# SDC_2.net
KiCad netlist of a schematic drawn in Altium Designer
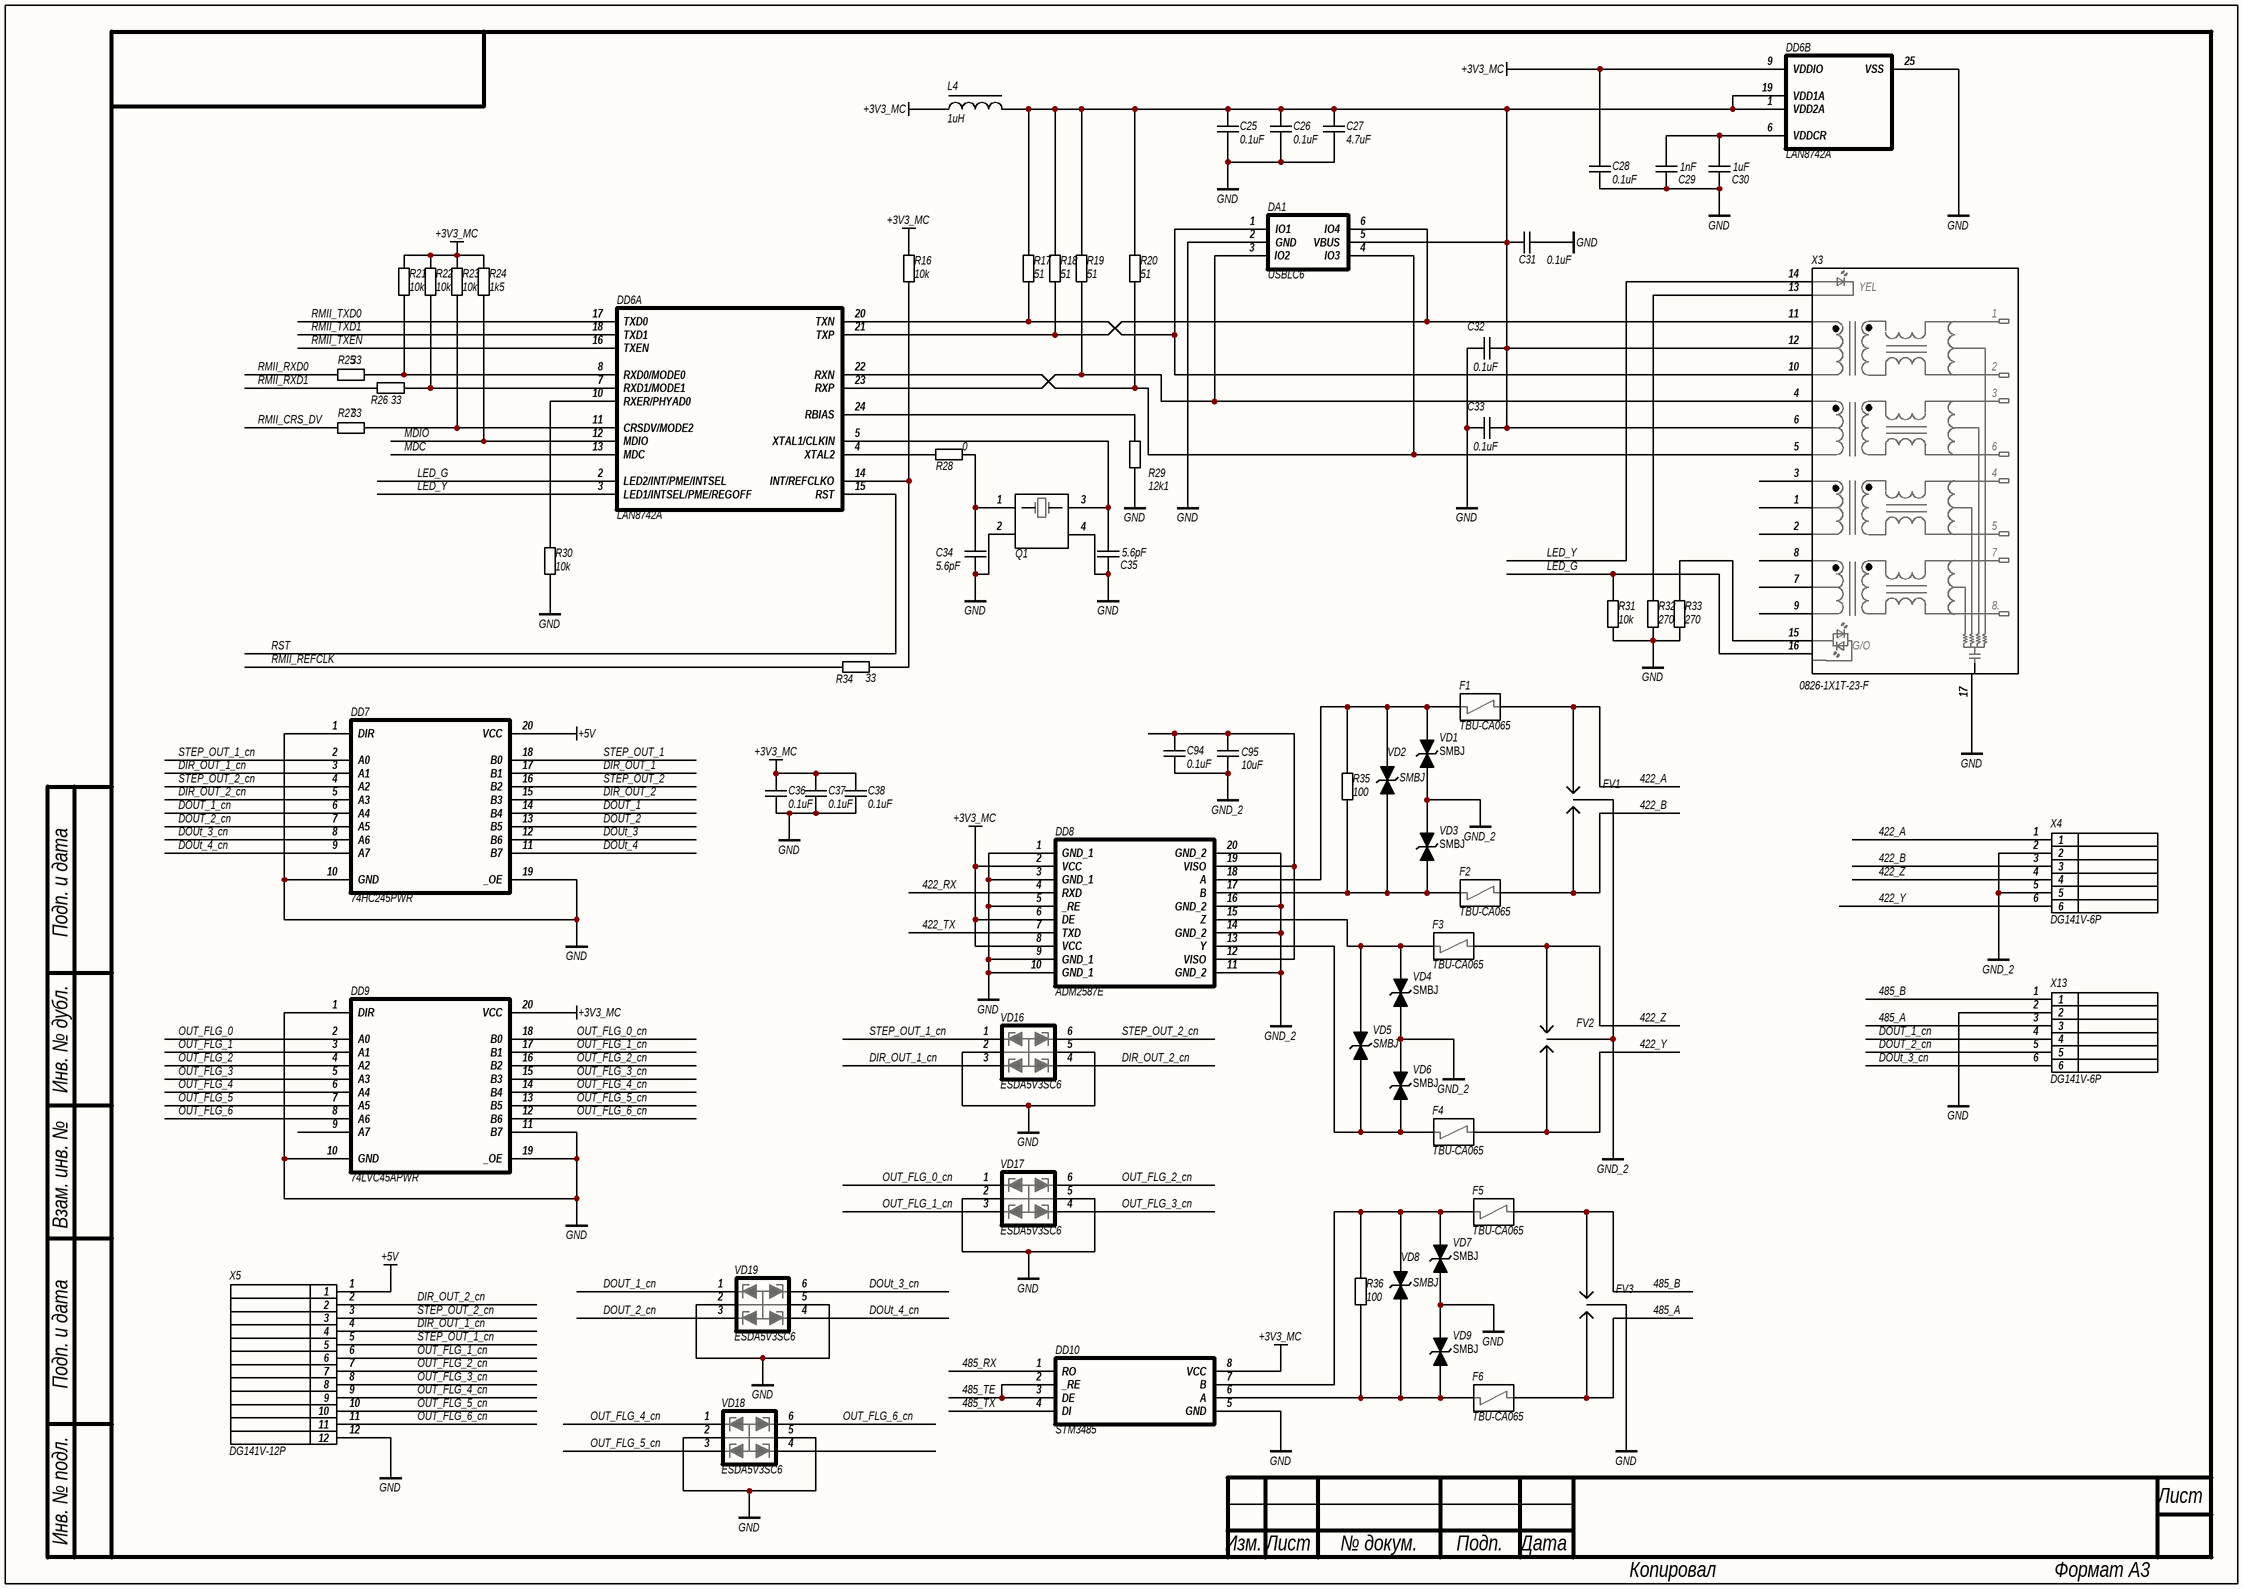
[diagram p0: SDC_2.SchDoc]

(export (version "E")
  (design (tool "Eeschema 10.0.6"))
  (components
    (comp (ref "C25")
      (value "0.1uF")
      (footprint "C0603")
      (description "SMD Capacitor")
      (fields (field (name "MANUFACTURER") "Murata") (field (name "TOLERANCE") "10%"))
      (libsource (lib "VKA") (part "CAP"))
    )
    (comp (ref "C26")
      (value "0.1uF")
      (footprint "C0603")
      (description "SMD Capacitor")
      (fields (field (name "MANUFACTURER") "Murata") (field (name "TOLERANCE") "10%"))
      (libsource (lib "VKA") (part "CAP"))
    )
    (comp (ref "C27")
      (value "4.7uF")
      (footprint "C0603")
      (description "SMD Capacitor")
      (fields (field (name "MANUFACTURER") "Murata") (field (name "TOLERANCE") "10%"))
      (libsource (lib "VKA") (part "CAP"))
    )
    (comp (ref "C28")
      (value "0.1uF")
      (footprint "C0603")
      (description "SMD Capacitor")
      (fields (field (name "MANUFACTURER") "Murata") (field (name "TOLERANCE") "10%"))
      (libsource (lib "VKA") (part "CAP"))
    )
    (comp (ref "C29")
      (value "1nF")
      (footprint "C0603")
      (description "SMD Capacitor")
      (fields (field (name "MANUFACTURER") "Murata") (field (name "TOLERANCE") "10%"))
      (libsource (lib "VKA") (part "CAP"))
    )
    (comp (ref "C30")
      (value "1uF")
      (footprint "C0603")
      (description "SMD Capacitor")
      (fields (field (name "MANUFACTURER") "Murata") (field (name "TOLERANCE") "10%"))
      (libsource (lib "VKA") (part "CAP"))
    )
    (comp (ref "C31")
      (value "0.1uF")
      (footprint "C0603")
      (description "SMD Capacitor")
      (fields (field (name "MANUFACTURER") "Murata") (field (name "TOLERANCE") "10%"))
      (libsource (lib "VKA") (part "CAP"))
    )
    (comp (ref "C32")
      (value "0.1uF")
      (footprint "C0603")
      (description "SMD Capacitor")
      (fields (field (name "MANUFACTURER") "Murata") (field (name "TOLERANCE") "10%"))
      (libsource (lib "VKA") (part "CAP"))
    )
    (comp (ref "C33")
      (value "0.1uF")
      (footprint "C0603")
      (description "SMD Capacitor")
      (fields (field (name "MANUFACTURER") "Murata") (field (name "TOLERANCE") "10%"))
      (libsource (lib "VKA") (part "CAP"))
    )
    (comp (ref "C34")
      (value "5.6pF")
      (footprint "C0603")
      (description "SMD Capacitor")
      (fields (field (name "MANUFACTURER") "Murata") (field (name "TOLERANCE") "10%"))
      (libsource (lib "VKA") (part "CAP"))
    )
    (comp (ref "C35")
      (value "5.6pF")
      (footprint "C0603")
      (description "SMD Capacitor")
      (fields (field (name "MANUFACTURER") "Murata") (field (name "TOLERANCE") "10%"))
      (libsource (lib "VKA") (part "CAP"))
    )
    (comp (ref "C36")
      (value "0.1uF")
      (footprint "C0603")
      (description "SMD Capacitor")
      (fields (field (name "MANUFACTURER") "Murata") (field (name "TOLERANCE") "10%"))
      (libsource (lib "VKA") (part "CAP"))
    )
    (comp (ref "C37")
      (value "0.1uF")
      (footprint "C0603")
      (description "SMD Capacitor")
      (fields (field (name "MANUFACTURER") "Murata") (field (name "TOLERANCE") "10%"))
      (libsource (lib "VKA") (part "CAP"))
    )
    (comp (ref "C38")
      (value "0.1uF")
      (footprint "C0603")
      (description "SMD Capacitor")
      (fields (field (name "MANUFACTURER") "Murata") (field (name "TOLERANCE") "10%"))
      (libsource (lib "VKA") (part "CAP"))
    )
    (comp (ref "C94")
      (value "0.1uF")
      (footprint "C0603")
      (description "SMD Capacitor")
      (fields (field (name "MANUFACTURER") "Murata") (field (name "TOLERANCE") "10%"))
      (libsource (lib "VKA") (part "CAP"))
    )
    (comp (ref "C95")
      (value "10uF")
      (footprint "C1210")
      (description "SMD Capacitor")
      (fields (field (name "MANUFACTURER") "Murata") (field (name "TOLERANCE") "10%"))
      (libsource (lib "VKA") (part "CAP"))
    )
    (comp (ref "DA1")
      (value "USBLC6")
      (footprint "ESD_SOT23-6L")
      (description "ESD protection Very low capacitance")
      (fields (field (name "MANUFACTURER") "ST"))
      (libsource (lib "VKA") (part "USBLC6-4SC6"))
    )
    (comp (ref "DD6")
      (value "LAN8742A")
      (footprint "QFN-MJ24")
      (description "RMII 10/100 Ethernet PHY")
      (libsource (lib "VKA") (part "LAN8742A"))
    )
    (comp (ref "DD7") (value "74HC245PWR") (footprint "TSSOP20") (libsource (lib "VKA") (part "74HC245PWR")))
    (comp (ref "DD8")
      (value "ADM2587E")
      (footprint "SOIC_20W")
      (description "RS485 isolator")
      (libsource (lib "VKA") (part "ADM2587E"))
    )
    (comp (ref "DD9")
      (value "74LVC45APWR")
      (footprint "TSSOP20")
      (libsource (lib "VKA") (part "74LVC45APWR"))
    )
    (comp (ref "DD10")
      (value "STM3485")
      (footprint "SO8_L")
      (description "RS485_tranciever")
      (libsource (lib "VKA") (part "ST3485EB"))
    )
    (comp (ref "F1")
      (value "TBU-CA065")
      (footprint "TBU-CA")
      (description "TBU fuse")
      (libsource (lib "VKA") (part "TBU-CA065"))
    )
    (comp (ref "F2")
      (value "TBU-CA065")
      (footprint "TBU-CA")
      (description "TBU fuse")
      (libsource (lib "VKA") (part "TBU-CA065"))
    )
    (comp (ref "F3")
      (value "TBU-CA065")
      (footprint "TBU-CA")
      (description "TBU fuse")
      (libsource (lib "VKA") (part "TBU-CA065"))
    )
    (comp (ref "F4")
      (value "TBU-CA065")
      (footprint "TBU-CA")
      (description "TBU fuse")
      (libsource (lib "VKA") (part "TBU-CA065"))
    )
    (comp (ref "F5")
      (value "TBU-CA065")
      (footprint "TBU-CA")
      (description "TBU fuse")
      (libsource (lib "VKA") (part "TBU-CA065"))
    )
    (comp (ref "F6")
      (value "TBU-CA065")
      (footprint "TBU-CA")
      (description "TBU fuse")
      (libsource (lib "VKA") (part "TBU-CA065"))
    )
    (comp (ref "FV1")
      (value "2030-42T-SM")
      (footprint "2030-42T-SM")
      (description "Charger")
      (libsource (lib "VKA") (part "2030-42T-SM"))
    )
    (comp (ref "FV2")
      (value "2030-42T-SM")
      (footprint "2030-42T-SM")
      (description "Charger")
      (libsource (lib "VKA") (part "2030-42T-SM"))
    )
    (comp (ref "FV3")
      (value "2030-42T-SM")
      (footprint "2030-42T-SM")
      (description "Charger")
      (libsource (lib "VKA") (part "2030-42T-SM"))
    )
    (comp (ref "L4")
      (value "1uH")
      (footprint "LQH32CN")
      (description "chip inductor")
      (fields (field (name "Comment") "LQH32CN"))
      (libsource (lib "VKA") (part "LQH32CN"))
    )
    (comp (ref "Q1")
      (value "NX2016SA")
      (footprint "CRY_NX2016SA_4P")
      (description "Crystal oscillator 25MHz")
      (fields (field (name "MANUFACTURER") "NDK"))
      (libsource (lib "VKA") (part "NX2016SA"))
    )
    (comp (ref "R16")
      (value "10k")
      (footprint "R0603")
      (description "SMD Resistor")
      (fields (field (name "POWER") "0.062 Wt") (field (name "TOLERANCE") "5%"))
      (libsource (lib "") (part "RES_1"))
    )
    (comp (ref "R17")
      (value "51")
      (footprint "R0603")
      (description "SMD Resistor")
      (fields (field (name "POWER") "0.062 Wt") (field (name "TOLERANCE") "5%"))
      (libsource (lib "VKA") (part "RES"))
    )
    (comp (ref "R18")
      (value "51")
      (footprint "R0603")
      (description "SMD Resistor")
      (fields (field (name "POWER") "0.062 Wt") (field (name "TOLERANCE") "5%"))
      (libsource (lib "VKA") (part "RES"))
    )
    (comp (ref "R19")
      (value "51")
      (footprint "R0603")
      (description "SMD Resistor")
      (fields (field (name "POWER") "0.062 Wt") (field (name "TOLERANCE") "5%"))
      (libsource (lib "VKA") (part "RES"))
    )
    (comp (ref "R20")
      (value "51")
      (footprint "R0603")
      (description "SMD Resistor")
      (fields (field (name "POWER") "0.062 Wt") (field (name "TOLERANCE") "5%"))
      (libsource (lib "VKA") (part "RES"))
    )
    (comp (ref "R21")
      (value "10k")
      (footprint "R0603")
      (description "SMD Resistor")
      (fields (field (name "POWER") "0.062 Wt") (field (name "TOLERANCE") "5%"))
      (libsource (lib "") (part "RES_1"))
    )
    (comp (ref "R22")
      (value "10k")
      (footprint "R0603")
      (description "SMD Resistor")
      (fields (field (name "POWER") "0.062 Wt") (field (name "TOLERANCE") "5%"))
      (libsource (lib "") (part "RES_1"))
    )
    (comp (ref "R23")
      (value "10k")
      (footprint "R0603")
      (description "SMD Resistor")
      (fields (field (name "POWER") "0.062 Wt") (field (name "TOLERANCE") "5%"))
      (libsource (lib "") (part "RES_1"))
    )
    (comp (ref "R24")
      (value "1k5")
      (footprint "R0603")
      (description "SMD Resistor")
      (fields (field (name "POWER") "0.062 Wt") (field (name "TOLERANCE") "5%"))
      (libsource (lib "") (part "RES_1"))
    )
    (comp (ref "R25")
      (value "33")
      (footprint "R0603")
      (description "SMD Resistor")
      (fields (field (name "POWER") "0.062 Wt") (field (name "TOLERANCE") "5%"))
      (libsource (lib "") (part "RES_2"))
    )
    (comp (ref "R26")
      (value "33")
      (footprint "R0603")
      (description "SMD Resistor")
      (fields (field (name "POWER") "0.062 Wt") (field (name "TOLERANCE") "5%"))
      (libsource (lib "") (part "RES_2"))
    )
    (comp (ref "R27")
      (value "33")
      (footprint "R0603")
      (description "SMD Resistor")
      (fields (field (name "POWER") "0.062 Wt") (field (name "TOLERANCE") "5%"))
      (libsource (lib "") (part "RES_2"))
    )
    (comp (ref "R28")
      (value "0")
      (footprint "R0603")
      (description "SMD Resistor")
      (fields (field (name "POWER") "0.062 Wt") (field (name "TOLERANCE") "5%"))
      (libsource (lib "") (part "RES_2"))
    )
    (comp (ref "R29")
      (value "12k1")
      (footprint "R0603")
      (description "SMD Resistor")
      (fields (field (name "POWER") "0.062 Wt") (field (name "TOLERANCE") "5%"))
      (libsource (lib "VKA") (part "RES"))
    )
    (comp (ref "R30")
      (value "10k")
      (footprint "R0603")
      (description "SMD Resistor")
      (fields (field (name "POWER") "0.062 Wt") (field (name "TOLERANCE") "5%"))
      (libsource (lib "VKA") (part "RES"))
    )
    (comp (ref "R31")
      (value "10k")
      (footprint "R0603")
      (description "SMD Resistor")
      (fields (field (name "POWER") "0.062 Wt") (field (name "TOLERANCE") "5%"))
      (libsource (lib "VKA") (part "RES"))
    )
    (comp (ref "R32")
      (value "270")
      (footprint "R0603")
      (description "SMD Resistor")
      (fields (field (name "POWER") "0.062 Wt") (field (name "TOLERANCE") "5%"))
      (libsource (lib "VKA") (part "RES"))
    )
    (comp (ref "R33")
      (value "270")
      (footprint "R0603")
      (description "SMD Resistor")
      (fields (field (name "POWER") "0.062 Wt") (field (name "TOLERANCE") "5%"))
      (libsource (lib "VKA") (part "RES"))
    )
    (comp (ref "R34")
      (value "33")
      (footprint "R0603")
      (description "SMD Resistor")
      (fields (field (name "POWER") "0.062 Wt") (field (name "TOLERANCE") "5%"))
      (libsource (lib "") (part "RES_2"))
    )
    (comp (ref "R35")
      (value "100")
      (footprint "R0603")
      (description "SMD Resistor")
      (fields (field (name "POWER") "0.062 Wt") (field (name "TOLERANCE") "5%"))
      (libsource (lib "") (part "RES_1"))
    )
    (comp (ref "R36")
      (value "100")
      (footprint "R0603")
      (description "SMD Resistor")
      (fields (field (name "POWER") "0.062 Wt") (field (name "TOLERANCE") "5%"))
      (libsource (lib "") (part "RES_1"))
    )
    (comp (ref "VD1")
      (value "SMBJ")
      (footprint "SMB-DO214")
      (description "TVS diode")
      (libsource (lib "VKA") (part "SMBJ5CA"))
    )
    (comp (ref "VD2")
      (value "SMBJ")
      (footprint "SMB-DO214")
      (description "TVSdiode")
      (libsource (lib "VKA") (part "SMBJ12CA"))
    )
    (comp (ref "VD3")
      (value "SMBJ")
      (footprint "SMB-DO214")
      (description "TVS diode")
      (libsource (lib "VKA") (part "SMBJ5CA"))
    )
    (comp (ref "VD4")
      (value "SMBJ")
      (footprint "SMB-DO214")
      (description "TVS diode")
      (libsource (lib "VKA") (part "SMBJ5CA"))
    )
    (comp (ref "VD5")
      (value "SMBJ")
      (footprint "SMB-DO214")
      (description "TVSdiode")
      (libsource (lib "VKA") (part "SMBJ12CA"))
    )
    (comp (ref "VD6")
      (value "SMBJ")
      (footprint "SMB-DO214")
      (description "TVS diode")
      (libsource (lib "VKA") (part "SMBJ5CA"))
    )
    (comp (ref "VD7")
      (value "SMBJ")
      (footprint "SMB-DO214")
      (description "TVS diode")
      (libsource (lib "VKA") (part "SMBJ5CA"))
    )
    (comp (ref "VD8")
      (value "SMBJ")
      (footprint "SMB-DO214")
      (description "TVSdiode")
      (libsource (lib "VKA") (part "SMBJ12CA"))
    )
    (comp (ref "VD9")
      (value "SMBJ")
      (footprint "SMB-DO214")
      (description "TVS diode")
      (libsource (lib "VKA") (part "SMBJ5CA"))
    )
    (comp (ref "VD16")
      (value "ESDA5V3SC6")
      (footprint "SOT23-6")
      (description "4-line ESD protection")
      (libsource (lib "VKA") (part "ESDA5V3SC6"))
    )
    (comp (ref "VD17")
      (value "ESDA5V3SC6")
      (footprint "SOT23-6")
      (description "4-line ESD protection")
      (libsource (lib "VKA") (part "ESDA5V3SC6"))
    )
    (comp (ref "VD18")
      (value "ESDA5V3SC6")
      (footprint "SOT23-6")
      (description "4-line ESD protection")
      (libsource (lib "VKA") (part "ESDA5V3SC6"))
    )
    (comp (ref "VD19")
      (value "ESDA5V3SC6")
      (footprint "SOT23-6")
      (description "4-line ESD protection")
      (libsource (lib "VKA") (part "ESDA5V3SC6"))
    )
    (comp (ref "X3")
      (value "0826-1X1T-23-F")
      (footprint "0826-1X1T-23F")
      (description "1Gb connector")
      (libsource (lib "VKA") (part "0826-1X1T-23-F"))
    )
    (comp (ref "X4")
      (value "DG141V-6P")
      (footprint "DG141V-06P")
      (description "wire connector")
      (libsource (lib "VKA") (part "DG141V-6P"))
    )
    (comp (ref "X5")
      (value "DG141V-12P")
      (footprint "DG141V-12P")
      (description "wire connector")
      (libsource (lib "VKA") (part "DG141V-12P"))
    )
    (comp (ref "X13")
      (value "DG141V-6P")
      (footprint "DG141V-06P")
      (description "wire connector")
      (libsource (lib "VKA") (part "DG141V-6P"))
    )
  )
  (nets
    (net (code "1") (name "+3V3_MC") (class "Default")
      (node (ref "C28") (pin "2") (pinfunction "2_2") (pintype "passive"))
      (node (ref "C36") (pin "2") (pinfunction "2_2") (pintype "passive"))
      (node (ref "C37") (pin "2") (pinfunction "2_2") (pintype "passive"))
      (node (ref "C38") (pin "2") (pinfunction "2_2") (pintype "passive"))
      (node (ref "DD10") (pin "8") (pinfunction "VCC_8") (pintype "passive"))
      (node (ref "DD6") (pin "9") (pinfunction "VDDIO_9") (pintype "passive"))
      (node (ref "DD8") (pin "2") (pinfunction "VCC_2") (pintype "passive"))
      (node (ref "DD8") (pin "6") (pinfunction "DE_6") (pintype "passive"))
      (node (ref "DD8") (pin "8") (pinfunction "VCC_8") (pintype "passive"))
      (node (ref "DD9") (pin "20") (pinfunction "VCC_20") (pintype "passive"))
      (node (ref "L4") (pin "1") (pinfunction "1_1") (pintype "passive"))
      (node (ref "R16") (pin "1") (pinfunction "1_1") (pintype "passive"))
      (node (ref "R21") (pin "1") (pinfunction "1_1") (pintype "passive"))
      (node (ref "R22") (pin "1") (pinfunction "1_1") (pintype "passive"))
      (node (ref "R23") (pin "1") (pinfunction "1_1") (pintype "passive"))
      (node (ref "R24") (pin "1") (pinfunction "1_1") (pintype "passive"))
    )
    (net (code "2") (name "+5V") (class "Default")
      (node (ref "DD7") (pin "20") (pinfunction "VCC_20") (pintype "passive"))
      (node (ref "X5") (pin "1") (pinfunction "1_1") (pintype "passive"))
    )
    (net (code "3") (name "/422_A") (class "Default")
      (node (ref "F1") (pin "2") (pinfunction "1_2") (pintype "passive"))
      (node (ref "FV1") (pin "3") (pinfunction "3_3") (pintype "passive"))
      (node (ref "X4") (pin "1") (pinfunction "1_1") (pintype "passive"))
    )
    (net (code "4") (name "/422_B") (class "Default")
      (node (ref "F2") (pin "2") (pinfunction "1_2") (pintype "passive"))
      (node (ref "FV1") (pin "1") (pinfunction "1_1") (pintype "passive"))
      (node (ref "X4") (pin "3") (pinfunction "3_3") (pintype "passive"))
    )
    (net (code "5") (name "/422_RX") (class "Default")
      (node (ref "DD8") (pin "4") (pinfunction "RXD_4") (pintype "passive"))
    )
    (net (code "6") (name "/422_TX") (class "Default")
      (node (ref "DD8") (pin "7") (pinfunction "TXD_7") (pintype "passive"))
    )
    (net (code "7") (name "/422_Y") (class "Default")
      (node (ref "F4") (pin "2") (pinfunction "1_2") (pintype "passive"))
      (node (ref "FV2") (pin "1") (pinfunction "1_1") (pintype "passive"))
      (node (ref "X4") (pin "6") (pinfunction "6_6") (pintype "passive"))
    )
    (net (code "8") (name "/422_Z") (class "Default")
      (node (ref "F3") (pin "2") (pinfunction "1_2") (pintype "passive"))
      (node (ref "FV2") (pin "3") (pinfunction "3_3") (pintype "passive"))
      (node (ref "X4") (pin "4") (pinfunction "4_4") (pintype "passive"))
    )
    (net (code "9") (name "/485_A") (class "Default")
      (node (ref "F6") (pin "2") (pinfunction "1_2") (pintype "passive"))
      (node (ref "FV3") (pin "1") (pinfunction "1_1") (pintype "passive"))
      (node (ref "X13") (pin "3") (pinfunction "3_3") (pintype "passive"))
    )
    (net (code "10") (name "/485_B") (class "Default")
      (node (ref "F5") (pin "2") (pinfunction "1_2") (pintype "passive"))
      (node (ref "FV3") (pin "3") (pinfunction "3_3") (pintype "passive"))
      (node (ref "X13") (pin "1") (pinfunction "1_1") (pintype "passive"))
    )
    (net (code "11") (name "/485_RX") (class "Default")
      (node (ref "DD10") (pin "1") (pinfunction "RO_1") (pintype "passive"))
    )
    (net (code "12") (name "/485_TE") (class "Default")
      (node (ref "DD10") (pin "2") (pinfunction "_RE_2") (pintype "passive"))
      (node (ref "DD10") (pin "3") (pinfunction "DE_3") (pintype "passive"))
    )
    (net (code "13") (name "/485_TX") (class "Default")
      (node (ref "DD10") (pin "4") (pinfunction "DI_4") (pintype "passive"))
    )
    (net (code "14") (name "/DIR_OUT_1") (class "Default")
      (node (ref "DD7") (pin "17") (pinfunction "B1_17") (pintype "passive"))
    )
    (net (code "15") (name "/DIR_OUT_1_cn") (class "Default")
      (node (ref "DD7") (pin "3") (pinfunction "A1_3") (pintype "passive"))
      (node (ref "VD16") (pin "3") (pinfunction "3_3") (pintype "passive"))
      (node (ref "X5") (pin "4") (pinfunction "4_4") (pintype "passive"))
    )
    (net (code "16") (name "/DIR_OUT_2") (class "Default")
      (node (ref "DD7") (pin "15") (pinfunction "B3_15") (pintype "passive"))
    )
    (net (code "17") (name "/DIR_OUT_2_cn") (class "Default")
      (node (ref "DD7") (pin "5") (pinfunction "A3_5") (pintype "passive"))
      (node (ref "VD16") (pin "4") (pinfunction "4_4") (pintype "passive"))
      (node (ref "X5") (pin "2") (pinfunction "2_2") (pintype "passive"))
    )
    (net (code "18") (name "/DOUT_1") (class "Default")
      (node (ref "DD7") (pin "14") (pinfunction "B4_14") (pintype "passive"))
    )
    (net (code "19") (name "/DOUT_1_cn") (class "Default")
      (node (ref "DD7") (pin "6") (pinfunction "A4_6") (pintype "passive"))
      (node (ref "VD19") (pin "1") (pinfunction "1_1") (pintype "passive"))
      (node (ref "X13") (pin "4") (pinfunction "4_4") (pintype "passive"))
    )
    (net (code "20") (name "/DOUT_2") (class "Default")
      (node (ref "DD7") (pin "13") (pinfunction "B5_13") (pintype "passive"))
    )
    (net (code "21") (name "/DOUT_2_cn") (class "Default")
      (node (ref "DD7") (pin "7") (pinfunction "A5_7") (pintype "passive"))
      (node (ref "VD19") (pin "3") (pinfunction "3_3") (pintype "passive"))
      (node (ref "X13") (pin "5") (pinfunction "5_5") (pintype "passive"))
    )
    (net (code "22") (name "/DOUt_3") (class "Default")
      (node (ref "DD7") (pin "12") (pinfunction "B6_12") (pintype "passive"))
    )
    (net (code "23") (name "/DOUt_3_cn") (class "Default")
      (node (ref "DD7") (pin "8") (pinfunction "A6_8") (pintype "passive"))
      (node (ref "VD19") (pin "6") (pinfunction "6_6") (pintype "passive"))
      (node (ref "X13") (pin "6") (pinfunction "6_6") (pintype "passive"))
    )
    (net (code "24") (name "/DOUt_4") (class "Default")
      (node (ref "DD7") (pin "11") (pinfunction "B7_11") (pintype "passive"))
    )
    (net (code "25") (name "/DOUt_4_cn") (class "Default")
      (node (ref "DD7") (pin "9") (pinfunction "A7_9") (pintype "passive"))
      (node (ref "VD19") (pin "4") (pinfunction "4_4") (pintype "passive"))
    )
    (net (code "26") (name "/LED_G") (class "Default")
      (node (ref "DD6") (pin "2") (pinfunction "LED2/INT/PME/INTSEL_2") (pintype "passive"))
      (node (ref "R31") (pin "2") (pinfunction "2_2") (pintype "passive"))
      (node (ref "X3") (pin "16") (pinfunction "16_16") (pintype "passive"))
    )
    (net (code "27") (name "/LED_Y") (class "Default")
      (node (ref "DD6") (pin "3") (pinfunction "LED1/INTSEL/PME/REGOFF_3") (pintype "passive"))
      (node (ref "X3") (pin "14") (pinfunction "14_14") (pintype "passive"))
    )
    (net (code "28") (name "/MDC") (class "Default")
      (node (ref "DD6") (pin "13") (pinfunction "MDC_13") (pintype "passive"))
    )
    (net (code "29") (name "/MDIO") (class "Default")
      (node (ref "DD6") (pin "12") (pinfunction "MDIO_12") (pintype "passive"))
      (node (ref "R24") (pin "2") (pinfunction "2_2") (pintype "passive"))
    )
    (net (code "30") (name "/OUT_FLG_0") (class "Default")
      (node (ref "DD9") (pin "2") (pinfunction "A0_2") (pintype "passive"))
    )
    (net (code "31") (name "/OUT_FLG_0_cn") (class "Default")
      (node (ref "DD9") (pin "18") (pinfunction "B0_18") (pintype "passive"))
      (node (ref "VD17") (pin "1") (pinfunction "1_1") (pintype "passive"))
    )
    (net (code "32") (name "/OUT_FLG_1") (class "Default")
      (node (ref "DD9") (pin "3") (pinfunction "A1_3") (pintype "passive"))
    )
    (net (code "33") (name "/OUT_FLG_1_cn") (class "Default")
      (node (ref "DD9") (pin "17") (pinfunction "B1_17") (pintype "passive"))
      (node (ref "VD17") (pin "3") (pinfunction "3_3") (pintype "passive"))
      (node (ref "X5") (pin "6") (pinfunction "6_6") (pintype "passive"))
    )
    (net (code "34") (name "/OUT_FLG_2") (class "Default")
      (node (ref "DD9") (pin "4") (pinfunction "A2_4") (pintype "passive"))
    )
    (net (code "35") (name "/OUT_FLG_2_cn") (class "Default")
      (node (ref "DD9") (pin "16") (pinfunction "B2_16") (pintype "passive"))
      (node (ref "VD17") (pin "6") (pinfunction "6_6") (pintype "passive"))
      (node (ref "X5") (pin "7") (pinfunction "7_7") (pintype "passive"))
    )
    (net (code "36") (name "/OUT_FLG_3") (class "Default")
      (node (ref "DD9") (pin "5") (pinfunction "A3_5") (pintype "passive"))
    )
    (net (code "37") (name "/OUT_FLG_3_cn") (class "Default")
      (node (ref "DD9") (pin "15") (pinfunction "B3_15") (pintype "passive"))
      (node (ref "VD17") (pin "4") (pinfunction "4_4") (pintype "passive"))
      (node (ref "X5") (pin "8") (pinfunction "8_8") (pintype "passive"))
    )
    (net (code "38") (name "/OUT_FLG_4") (class "Default")
      (node (ref "DD9") (pin "6") (pinfunction "A4_6") (pintype "passive"))
    )
    (net (code "39") (name "/OUT_FLG_4_cn") (class "Default")
      (node (ref "DD9") (pin "14") (pinfunction "B4_14") (pintype "passive"))
      (node (ref "VD18") (pin "1") (pinfunction "1_1") (pintype "passive"))
      (node (ref "X5") (pin "9") (pinfunction "9_9") (pintype "passive"))
    )
    (net (code "40") (name "/OUT_FLG_5") (class "Default")
      (node (ref "DD9") (pin "7") (pinfunction "A5_7") (pintype "passive"))
    )
    (net (code "41") (name "/OUT_FLG_5_cn") (class "Default")
      (node (ref "DD9") (pin "13") (pinfunction "B5_13") (pintype "passive"))
      (node (ref "VD18") (pin "3") (pinfunction "3_3") (pintype "passive"))
      (node (ref "X5") (pin "10") (pinfunction "10_10") (pintype "passive"))
    )
    (net (code "42") (name "/OUT_FLG_6") (class "Default")
      (node (ref "DD9") (pin "8") (pinfunction "A6_8") (pintype "passive"))
    )
    (net (code "43") (name "/OUT_FLG_6_cn") (class "Default")
      (node (ref "DD9") (pin "12") (pinfunction "B6_12") (pintype "passive"))
      (node (ref "VD18") (pin "6") (pinfunction "6_6") (pintype "passive"))
      (node (ref "X5") (pin "11") (pinfunction "11_11") (pintype "passive"))
    )
    (net (code "44") (name "/RMII_CRS_DV") (class "Default")
      (node (ref "R27") (pin "2") (pinfunction "2_2") (pintype "passive"))
    )
    (net (code "45") (name "/RMII_REFCLK") (class "Default")
      (node (ref "R34") (pin "2") (pinfunction "2_2") (pintype "passive"))
    )
    (net (code "46") (name "/RMII_RXD0") (class "Default")
      (node (ref "R25") (pin "2") (pinfunction "2_2") (pintype "passive"))
    )
    (net (code "47") (name "/RMII_RXD1") (class "Default")
      (node (ref "R26") (pin "2") (pinfunction "2_2") (pintype "passive"))
    )
    (net (code "48") (name "/RMII_TXD0") (class "Default")
      (node (ref "DD6") (pin "17") (pinfunction "TXD0_17") (pintype "passive"))
    )
    (net (code "49") (name "/RMII_TXD1") (class "Default")
      (node (ref "DD6") (pin "18") (pinfunction "TXD1_18") (pintype "passive"))
    )
    (net (code "50") (name "/RMII_TXEN") (class "Default")
      (node (ref "DD6") (pin "16") (pinfunction "TXEN_16") (pintype "passive"))
    )
    (net (code "51") (name "/RST") (class "Default")
      (node (ref "DD6") (pin "15") (pinfunction "RST_15") (pintype "passive"))
    )
    (net (code "52") (name "/STEP_OUT_1") (class "Default")
      (node (ref "DD7") (pin "18") (pinfunction "B0_18") (pintype "passive"))
    )
    (net (code "53") (name "/STEP_OUT_1_cn") (class "Default")
      (node (ref "DD7") (pin "2") (pinfunction "A0_2") (pintype "passive"))
      (node (ref "VD16") (pin "1") (pinfunction "1_1") (pintype "passive"))
      (node (ref "X5") (pin "5") (pinfunction "5_5") (pintype "passive"))
    )
    (net (code "54") (name "/STEP_OUT_2") (class "Default")
      (node (ref "DD7") (pin "16") (pinfunction "B2_16") (pintype "passive"))
    )
    (net (code "55") (name "/STEP_OUT_2_cn") (class "Default")
      (node (ref "DD7") (pin "4") (pinfunction "A2_4") (pintype "passive"))
      (node (ref "VD16") (pin "6") (pinfunction "6_6") (pintype "passive"))
      (node (ref "X5") (pin "3") (pinfunction "3_3") (pintype "passive"))
    )
    (net (code "56") (name "GND") (class "Default")
      (node (ref "C25") (pin "1") (pinfunction "1_1") (pintype "passive"))
      (node (ref "C26") (pin "1") (pinfunction "1_1") (pintype "passive"))
      (node (ref "C27") (pin "1") (pinfunction "1_1") (pintype "passive"))
      (node (ref "C28") (pin "1") (pinfunction "1_1") (pintype "passive"))
      (node (ref "C29") (pin "1") (pinfunction "1_1") (pintype "passive"))
      (node (ref "C30") (pin "1") (pinfunction "1_1") (pintype "passive"))
      (node (ref "C31") (pin "2") (pinfunction "2_2") (pintype "passive"))
      (node (ref "C32") (pin "1") (pinfunction "1_1") (pintype "passive"))
      (node (ref "C33") (pin "1") (pinfunction "1_1") (pintype "passive"))
      (node (ref "C34") (pin "1") (pinfunction "1_1") (pintype "passive"))
      (node (ref "C35") (pin "1") (pinfunction "1_1") (pintype "passive"))
      (node (ref "C36") (pin "1") (pinfunction "1_1") (pintype "passive"))
      (node (ref "C37") (pin "1") (pinfunction "1_1") (pintype "passive"))
      (node (ref "C38") (pin "1") (pinfunction "1_1") (pintype "passive"))
      (node (ref "DA1") (pin "2") (pinfunction "GND_2") (pintype "passive"))
      (node (ref "DD10") (pin "5") (pinfunction "GND_5") (pintype "passive"))
      (node (ref "DD6") (pin "25") (pinfunction "VSS_25") (pintype "passive"))
      (node (ref "DD7") (pin "1") (pinfunction "DIR_1") (pintype "passive"))
      (node (ref "DD7") (pin "10") (pinfunction "GND_10") (pintype "passive"))
      (node (ref "DD7") (pin "19") (pinfunction "_OE_19") (pintype "passive"))
      (node (ref "DD8") (pin "1") (pinfunction "GND_1_1") (pintype "passive"))
      (node (ref "DD8") (pin "10") (pinfunction "GND_1_10") (pintype "passive"))
      (node (ref "DD8") (pin "3") (pinfunction "GND_1_3") (pintype "passive"))
      (node (ref "DD8") (pin "5") (pinfunction "_RE_5") (pintype "passive"))
      (node (ref "DD8") (pin "9") (pinfunction "GND_1_9") (pintype "passive"))
      (node (ref "DD9") (pin "1") (pinfunction "DIR_1") (pintype "passive"))
      (node (ref "DD9") (pin "10") (pinfunction "GND_10") (pintype "passive"))
      (node (ref "DD9") (pin "11") (pinfunction "B7_11") (pintype "passive"))
      (node (ref "DD9") (pin "19") (pinfunction "_OE_19") (pintype "passive"))
      (node (ref "FV3") (pin "2") (pinfunction "2_2") (pintype "passive"))
      (node (ref "Q1") (pin "2") (pinfunction "OSC1_2") (pintype "passive"))
      (node (ref "Q1") (pin "4") (pinfunction "OSC1_4") (pintype "passive"))
      (node (ref "R29") (pin "1") (pinfunction "1_1") (pintype "passive"))
      (node (ref "R30") (pin "1") (pinfunction "1_1") (pintype "passive"))
      (node (ref "R31") (pin "1") (pinfunction "1_1") (pintype "passive"))
      (node (ref "R32") (pin "1") (pinfunction "1_1") (pintype "passive"))
      (node (ref "R33") (pin "1") (pinfunction "1_1") (pintype "passive"))
      (node (ref "VD16") (pin "2") (pinfunction "2_2") (pintype "passive"))
      (node (ref "VD16") (pin "5") (pinfunction "5_5") (pintype "passive"))
      (node (ref "VD17") (pin "2") (pinfunction "2_2") (pintype "passive"))
      (node (ref "VD17") (pin "5") (pinfunction "5_5") (pintype "passive"))
      (node (ref "VD18") (pin "2") (pinfunction "2_2") (pintype "passive"))
      (node (ref "VD18") (pin "5") (pinfunction "5_5") (pintype "passive"))
      (node (ref "VD19") (pin "2") (pinfunction "2_2") (pintype "passive"))
      (node (ref "VD19") (pin "5") (pinfunction "5_5") (pintype "passive"))
      (node (ref "VD7") (pin "1") (pinfunction "A_1") (pintype "passive"))
      (node (ref "VD9") (pin "2") (pinfunction "B_2") (pintype "passive"))
      (node (ref "X13") (pin "2") (pinfunction "2_2") (pintype "passive"))
      (node (ref "X3") (pin "17") (pinfunction "17_17") (pintype "passive"))
      (node (ref "X5") (pin "12") (pinfunction "12_12") (pintype "passive"))
    )
    (net (code "57") (name "GND_2") (class "Default")
      (node (ref "C94") (pin "1") (pinfunction "1_1") (pintype "passive"))
      (node (ref "C95") (pin "1") (pinfunction "1_1") (pintype "passive"))
      (node (ref "DD8") (pin "11") (pinfunction "GND_2_11") (pintype "passive"))
      (node (ref "DD8") (pin "14") (pinfunction "GND_2_14") (pintype "passive"))
      (node (ref "DD8") (pin "16") (pinfunction "GND_2_16") (pintype "passive"))
      (node (ref "DD8") (pin "20") (pinfunction "GND_2_20") (pintype "passive"))
      (node (ref "FV1") (pin "2") (pinfunction "2_2") (pintype "passive"))
      (node (ref "FV2") (pin "2") (pinfunction "2_2") (pintype "passive"))
      (node (ref "VD1") (pin "1") (pinfunction "A_1") (pintype "passive"))
      (node (ref "VD3") (pin "2") (pinfunction "B_2") (pintype "passive"))
      (node (ref "VD4") (pin "1") (pinfunction "A_1") (pintype "passive"))
      (node (ref "VD6") (pin "2") (pinfunction "B_2") (pintype "passive"))
      (node (ref "X4") (pin "2") (pinfunction "2_2") (pintype "passive"))
      (node (ref "X4") (pin "5") (pinfunction "5_5") (pintype "passive"))
    )
    (net (code "58") (name "Net-(C34-Pad2)") (class "Default")
      (node (ref "C34") (pin "2") (pinfunction "2_2") (pintype "passive"))
      (node (ref "Q1") (pin "1") (pinfunction "OSC1_1") (pintype "passive"))
      (node (ref "R28") (pin "1") (pinfunction "1_1") (pintype "passive"))
    )
    (net (code "59") (name "Net-(C94-Pad2)") (class "Default")
      (node (ref "C94") (pin "2") (pinfunction "2_2") (pintype "passive"))
      (node (ref "C95") (pin "2") (pinfunction "2_2") (pintype "passive"))
      (node (ref "DD8") (pin "12") (pinfunction "VISO_12") (pintype "passive"))
      (node (ref "DD8") (pin "19") (pinfunction "VISO_19") (pintype "passive"))
    )
    (net (code "60") (name "Net-(DA1-IO1)") (class "Default")
      (node (ref "DA1") (pin "1") (pinfunction "IO1_1") (pintype "passive"))
      (node (ref "DD6") (pin "20") (pinfunction "TXN_20") (pintype "passive"))
      (node (ref "R17") (pin "1") (pinfunction "1_1") (pintype "passive"))
      (node (ref "X3") (pin "10") (pinfunction "10_10") (pintype "passive"))
    )
    (net (code "61") (name "Net-(DA1-IO2)") (class "Default")
      (node (ref "DA1") (pin "3") (pinfunction "IO2_3") (pintype "passive"))
      (node (ref "DD6") (pin "23") (pinfunction "RXP_23") (pintype "passive"))
      (node (ref "R19") (pin "1") (pinfunction "1_1") (pintype "passive"))
      (node (ref "X3") (pin "4") (pinfunction "4_4") (pintype "passive"))
    )
    (net (code "62") (name "Net-(DA1-IO3)") (class "Default")
      (node (ref "DA1") (pin "4") (pinfunction "IO3_4") (pintype "passive"))
      (node (ref "DD6") (pin "22") (pinfunction "RXN_22") (pintype "passive"))
      (node (ref "R20") (pin "1") (pinfunction "1_1") (pintype "passive"))
      (node (ref "X3") (pin "5") (pinfunction "5_5") (pintype "passive"))
    )
    (net (code "63") (name "Net-(DA1-IO4)") (class "Default")
      (node (ref "DA1") (pin "6") (pinfunction "IO4_6") (pintype "passive"))
      (node (ref "DD6") (pin "21") (pinfunction "TXP_21") (pintype "passive"))
      (node (ref "R18") (pin "1") (pinfunction "1_1") (pintype "passive"))
      (node (ref "X3") (pin "11") (pinfunction "11_11") (pintype "passive"))
    )
    (net (code "64") (name "Net-(DA1-VBUS)") (class "Default")
      (node (ref "C25") (pin "2") (pinfunction "2_2") (pintype "passive"))
      (node (ref "C26") (pin "2") (pinfunction "2_2") (pintype "passive"))
      (node (ref "C27") (pin "2") (pinfunction "2_2") (pintype "passive"))
      (node (ref "C31") (pin "1") (pinfunction "1_1") (pintype "passive"))
      (node (ref "C32") (pin "2") (pinfunction "2_2") (pintype "passive"))
      (node (ref "C33") (pin "2") (pinfunction "2_2") (pintype "passive"))
      (node (ref "DA1") (pin "5") (pinfunction "VBUS_5") (pintype "passive"))
      (node (ref "DD6") (pin "1") (pinfunction "VDD2A_1") (pintype "passive"))
      (node (ref "DD6") (pin "19") (pinfunction "VDD1A_19") (pintype "passive"))
      (node (ref "L4") (pin "2") (pinfunction "2_2") (pintype "passive"))
      (node (ref "R17") (pin "2") (pinfunction "2_2") (pintype "passive"))
      (node (ref "R18") (pin "2") (pinfunction "2_2") (pintype "passive"))
      (node (ref "R19") (pin "2") (pinfunction "2_2") (pintype "passive"))
      (node (ref "R20") (pin "2") (pinfunction "2_2") (pintype "passive"))
      (node (ref "X3") (pin "12") (pinfunction "12_12") (pintype "passive"))
      (node (ref "X3") (pin "6") (pinfunction "6_6") (pintype "passive"))
    )
    (net (code "65") (name "Net-(DD6A-CRSDV{slash}MODE2)") (class "Default")
      (node (ref "DD6") (pin "11") (pinfunction "CRSDV/MODE2_11") (pintype "passive"))
      (node (ref "R23") (pin "2") (pinfunction "2_2") (pintype "passive"))
      (node (ref "R27") (pin "1") (pinfunction "1_1") (pintype "passive"))
    )
    (net (code "66") (name "Net-(DD6A-INT{slash}REFCLKO)") (class "Default")
      (node (ref "DD6") (pin "14") (pinfunction "INT/REFCLKO_14") (pintype "passive"))
      (node (ref "R16") (pin "2") (pinfunction "2_2") (pintype "passive"))
      (node (ref "R34") (pin "1") (pinfunction "1_1") (pintype "passive"))
    )
    (net (code "67") (name "Net-(DD6A-RBIAS)") (class "Default")
      (node (ref "DD6") (pin "24") (pinfunction "RBIAS_24") (pintype "passive"))
      (node (ref "R29") (pin "2") (pinfunction "2_2") (pintype "passive"))
    )
    (net (code "68") (name "Net-(DD6A-RXD0{slash}MODE0)") (class "Default")
      (node (ref "DD6") (pin "8") (pinfunction "RXD0/MODE0_8") (pintype "passive"))
      (node (ref "R21") (pin "2") (pinfunction "2_2") (pintype "passive"))
      (node (ref "R25") (pin "1") (pinfunction "1_1") (pintype "passive"))
    )
    (net (code "69") (name "Net-(DD6A-RXD1{slash}MODE1)") (class "Default")
      (node (ref "DD6") (pin "7") (pinfunction "RXD1/MODE1_7") (pintype "passive"))
      (node (ref "R22") (pin "2") (pinfunction "2_2") (pintype "passive"))
      (node (ref "R26") (pin "1") (pinfunction "1_1") (pintype "passive"))
    )
    (net (code "70") (name "Net-(DD6A-RXER{slash}PHYAD0)") (class "Default")
      (node (ref "DD6") (pin "10") (pinfunction "RXER/PHYAD0_10") (pintype "passive"))
      (node (ref "R30") (pin "2") (pinfunction "2_2") (pintype "passive"))
    )
    (net (code "71") (name "Net-(DD6A-XTAL1{slash}CLKIN)") (class "Default")
      (node (ref "C35") (pin "2") (pinfunction "2_2") (pintype "passive"))
      (node (ref "DD6") (pin "5") (pinfunction "XTAL1/CLKIN_5") (pintype "passive"))
      (node (ref "Q1") (pin "3") (pinfunction "OSC2_3") (pintype "passive"))
    )
    (net (code "72") (name "Net-(DD6A-XTAL2)") (class "Default")
      (node (ref "DD6") (pin "4") (pinfunction "XTAL2_4") (pintype "passive"))
      (node (ref "R28") (pin "2") (pinfunction "2_2") (pintype "passive"))
    )
    (net (code "73") (name "Net-(DD6B-VDDCR)") (class "Default")
      (node (ref "C29") (pin "2") (pinfunction "2_2") (pintype "passive"))
      (node (ref "C30") (pin "2") (pinfunction "2_2") (pintype "passive"))
      (node (ref "DD6") (pin "6") (pinfunction "VDDCR_6") (pintype "passive"))
    )
    (net (code "74") (name "Net-(DD8-A)") (class "Default")
      (node (ref "DD8") (pin "18") (pinfunction "A_18") (pintype "passive"))
      (node (ref "F1") (pin "1") (pinfunction "1_1") (pintype "passive"))
      (node (ref "R35") (pin "1") (pinfunction "1_1") (pintype "passive"))
      (node (ref "VD1") (pin "2") (pinfunction "B_2") (pintype "passive"))
      (node (ref "VD2") (pin "2") (pinfunction "B_2") (pintype "passive"))
    )
    (net (code "75") (name "Net-(DD8-B)") (class "Default")
      (node (ref "DD8") (pin "17") (pinfunction "B_17") (pintype "passive"))
      (node (ref "F2") (pin "1") (pinfunction "1_1") (pintype "passive"))
      (node (ref "R35") (pin "2") (pinfunction "2_2") (pintype "passive"))
      (node (ref "VD2") (pin "1") (pinfunction "A_1") (pintype "passive"))
      (node (ref "VD3") (pin "1") (pinfunction "A_1") (pintype "passive"))
    )
    (net (code "76") (name "Net-(DD8-Y)") (class "Default")
      (node (ref "DD8") (pin "13") (pinfunction "Y_13") (pintype "passive"))
      (node (ref "F4") (pin "1") (pinfunction "1_1") (pintype "passive"))
      (node (ref "VD5") (pin "1") (pinfunction "A_1") (pintype "passive"))
      (node (ref "VD6") (pin "1") (pinfunction "A_1") (pintype "passive"))
    )
    (net (code "77") (name "Net-(DD8-Z)") (class "Default")
      (node (ref "DD8") (pin "15") (pinfunction "Z_15") (pintype "passive"))
      (node (ref "F3") (pin "1") (pinfunction "1_1") (pintype "passive"))
      (node (ref "VD4") (pin "2") (pinfunction "B_2") (pintype "passive"))
      (node (ref "VD5") (pin "2") (pinfunction "B_2") (pintype "passive"))
    )
    (net (code "78") (name "Net-(DD10-A)") (class "Default")
      (node (ref "DD10") (pin "6") (pinfunction "A_6") (pintype "passive"))
      (node (ref "F6") (pin "1") (pinfunction "1_1") (pintype "passive"))
      (node (ref "R36") (pin "2") (pinfunction "2_2") (pintype "passive"))
      (node (ref "VD8") (pin "1") (pinfunction "A_1") (pintype "passive"))
      (node (ref "VD9") (pin "1") (pinfunction "A_1") (pintype "passive"))
    )
    (net (code "79") (name "Net-(DD10-B)") (class "Default")
      (node (ref "DD10") (pin "7") (pinfunction "B_7") (pintype "passive"))
      (node (ref "F5") (pin "1") (pinfunction "1_1") (pintype "passive"))
      (node (ref "R36") (pin "1") (pinfunction "1_1") (pintype "passive"))
      (node (ref "VD7") (pin "2") (pinfunction "B_2") (pintype "passive"))
      (node (ref "VD8") (pin "2") (pinfunction "B_2") (pintype "passive"))
    )
    (net (code "80") (name "Net-(R32-Pad2)") (class "Default")
      (node (ref "R32") (pin "2") (pinfunction "2_2") (pintype "passive"))
      (node (ref "X3") (pin "13") (pinfunction "13_13") (pintype "passive"))
    )
    (net (code "81") (name "Net-(R33-Pad2)") (class "Default")
      (node (ref "R33") (pin "2") (pinfunction "2_2") (pintype "passive"))
      (node (ref "X3") (pin "15") (pinfunction "15_15") (pintype "passive"))
    )
    (net (code "82") (name "unconnected-(DD9-A7-Pad9)") (class "Default")
      (node (ref "DD9") (pin "9") (pinfunction "A7_9") (pintype "passive"))
    )
    (net (code "83") (name "unconnected-(VD18-Pad4)") (class "Default")
      (node (ref "VD18") (pin "4") (pinfunction "4_4") (pintype "passive"))
    )
    (net (code "84") (name "unconnected-(X3-Pad1)") (class "Default")
      (node (ref "X3") (pin "1") (pinfunction "1_1") (pintype "passive"))
    )
    (net (code "85") (name "unconnected-(X3-Pad2)") (class "Default")
      (node (ref "X3") (pin "2") (pinfunction "2_2") (pintype "passive"))
    )
    (net (code "86") (name "unconnected-(X3-Pad3)") (class "Default")
      (node (ref "X3") (pin "3") (pinfunction "3_3") (pintype "passive"))
    )
    (net (code "87") (name "unconnected-(X3-Pad7)") (class "Default")
      (node (ref "X3") (pin "7") (pinfunction "7_7") (pintype "passive"))
    )
    (net (code "88") (name "unconnected-(X3-Pad8)") (class "Default")
      (node (ref "X3") (pin "8") (pinfunction "8_8") (pintype "passive"))
    )
    (net (code "89") (name "unconnected-(X3-Pad9)") (class "Default")
      (node (ref "X3") (pin "9") (pinfunction "9_9") (pintype "passive"))
    )
  )
)
